# Altium_Demo_-_ADC_Schematic.net
KiCad netlist of a schematic drawn in Altium Designer
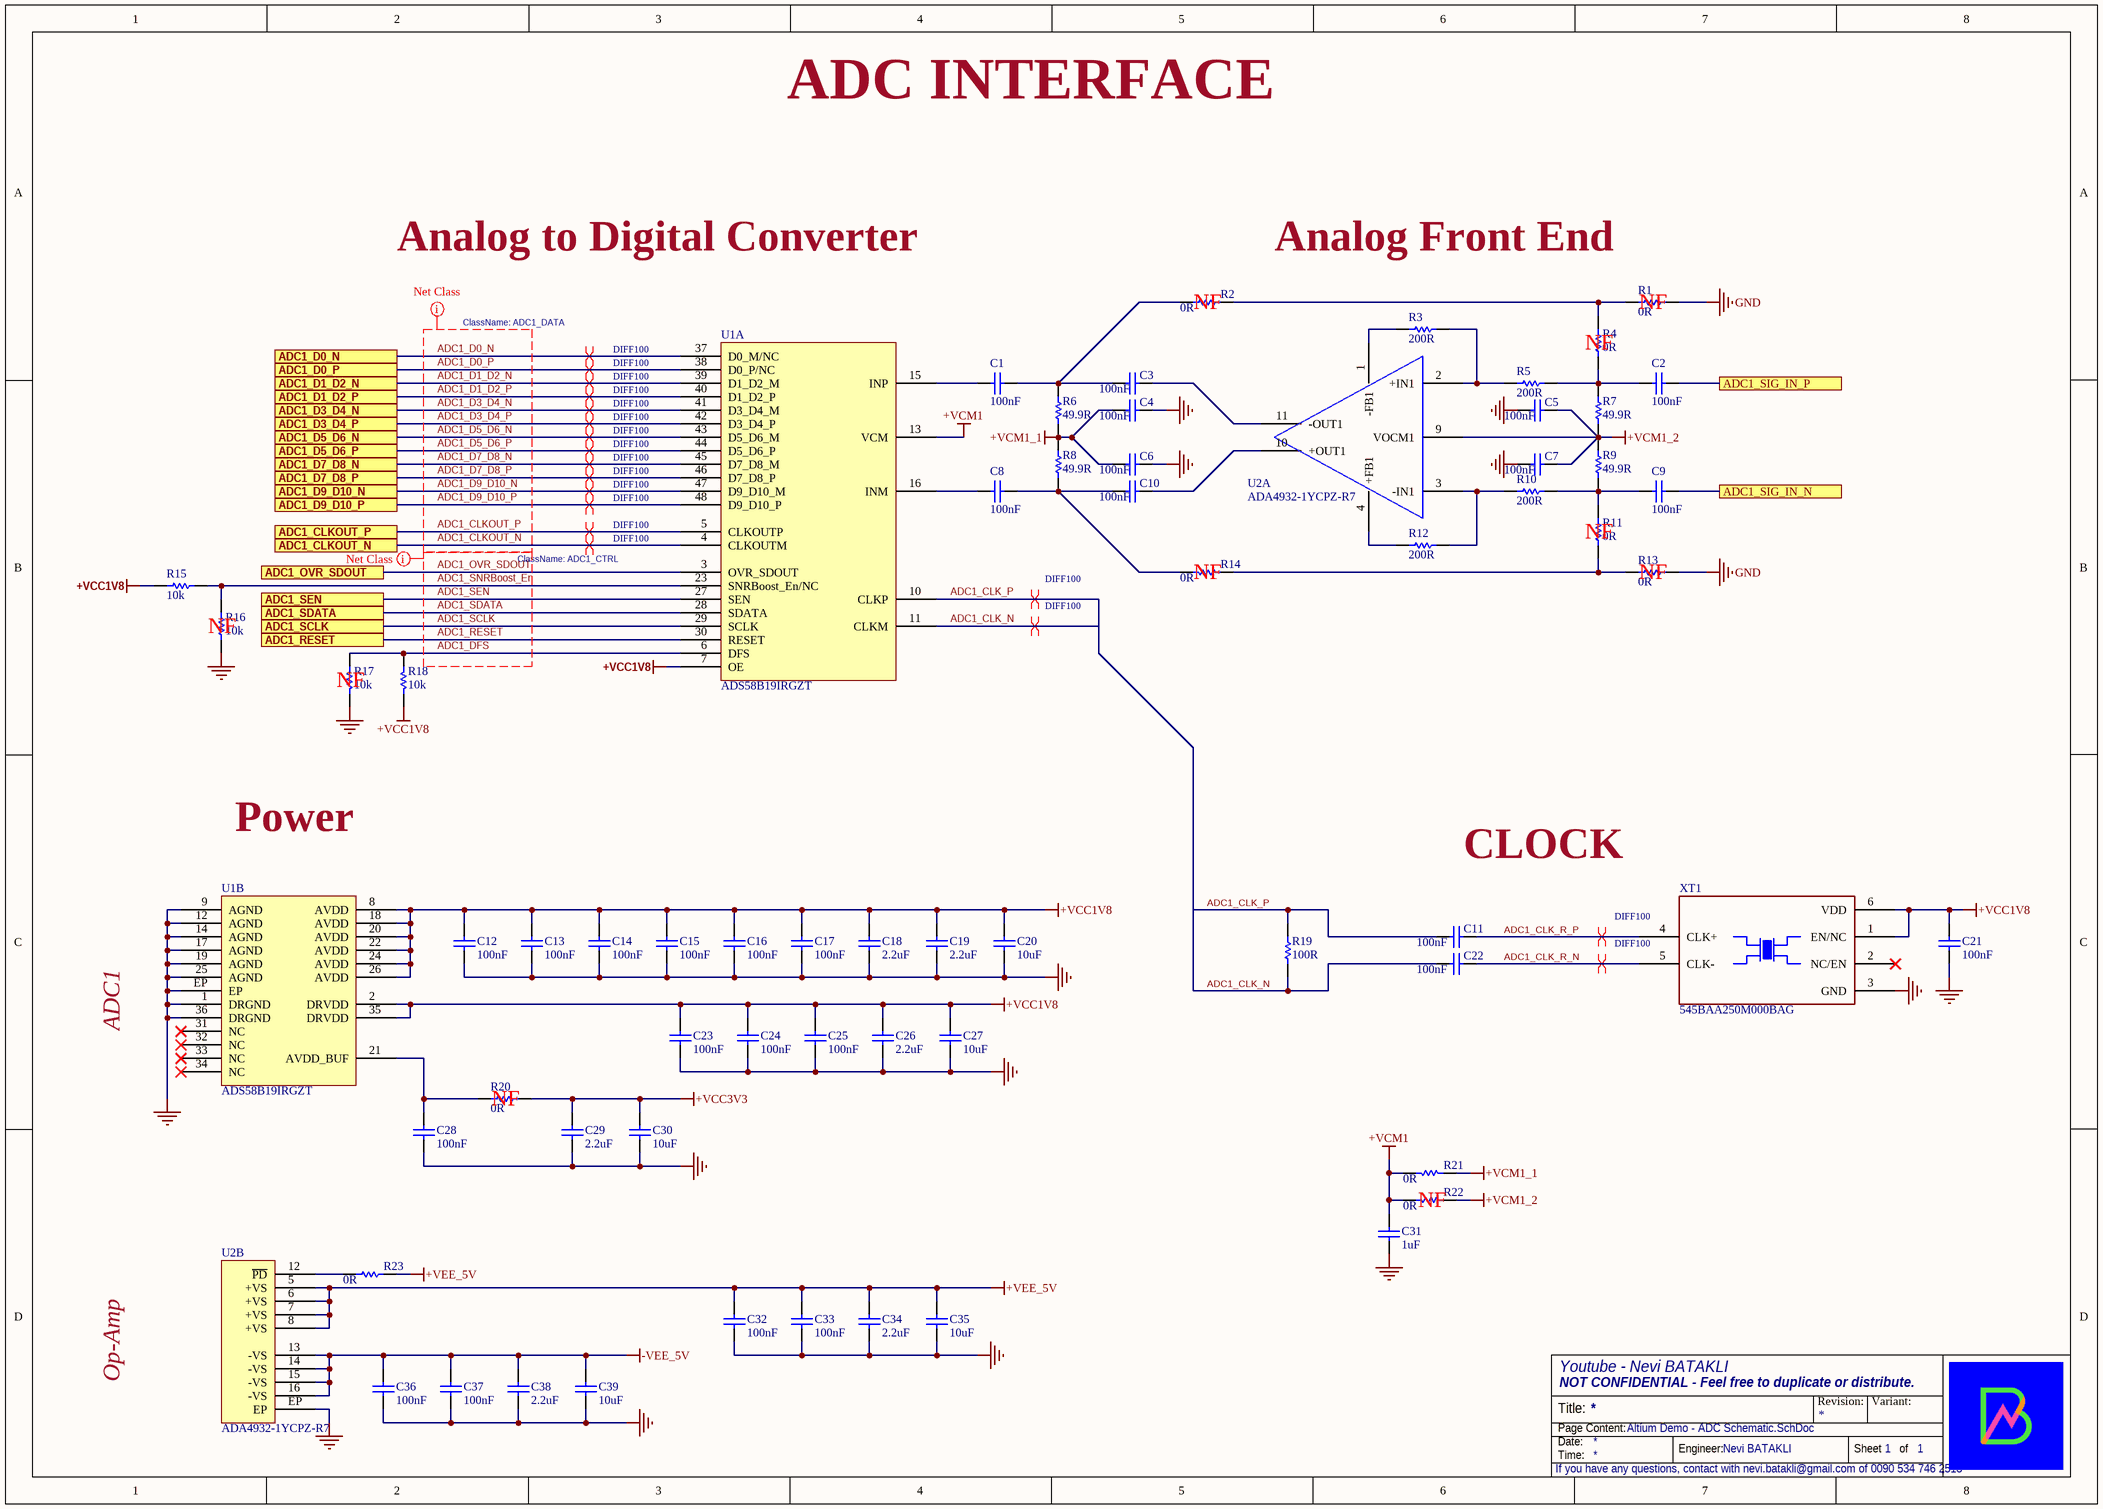
[diagram p0: Altium Demo - ADC Schematic.SchDoc]

(export (version "E")
  (design (tool "Eeschema 10.0.6"))
  (components
    (comp (ref "C1")
      (value "100nF")
      (footprint "R0201")
      (description "CAP CER 0.1UF 25V X6S 0201")
      (fields (field (name "TOLERANCE") "20%"))
      (libsource (lib "Capacitors") (part "GRM033C81E104ME14D"))
    )
    (comp (ref "C2")
      (value "100nF")
      (footprint "C0201")
      (description "CAP CER 0.1UF 25V X6S 0201")
      (fields (field (name "TOLERANCE") "20%"))
      (libsource (lib "Capacitors") (part "GRM033C81E104ME14D"))
    )
    (comp (ref "C3")
      (value "100nF")
      (footprint "C0201")
      (description "CAP CER 0.1UF 25V X6S 0201")
      (fields (field (name "TOLERANCE") "20%"))
      (libsource (lib "Capacitors") (part "GRM033C81E104ME14D"))
    )
    (comp (ref "C4")
      (value "100nF")
      (footprint "C0402")
      (description "Cap Ceramic 0.1uF 16V X7R 10% SMD 0402 125C Paper T/R")
      (fields
        (field (name "MANUFACTURER") "Samsung")
        (field (name "MANUFACTURER PART NUMBER") "CL05B104KO5NNNC")
        (field (name ".CREATOR") "NB")
      )
      (libsource (lib "Capacitors") (part "CL05B104KO5NNNC"))
    )
    (comp (ref "C5")
      (value "100nF")
      (footprint "C0402")
      (description "Cap Ceramic 0.1uF 16V X7R 10% SMD 0402 125C Paper T/R")
      (fields
        (field (name "MANUFACTURER") "Samsung")
        (field (name "MANUFACTURER PART NUMBER") "CL05B104KO5NNNC")
        (field (name ".CREATOR") "NB")
      )
      (libsource (lib "Capacitors") (part "CL05B104KO5NNNC"))
    )
    (comp (ref "C6")
      (value "100nF")
      (footprint "C0402")
      (description "Cap Ceramic 0.1uF 16V X7R 10% SMD 0402 125C Paper T/R")
      (fields
        (field (name "MANUFACTURER") "Samsung")
        (field (name "MANUFACTURER PART NUMBER") "CL05B104KO5NNNC")
        (field (name ".CREATOR") "NB")
      )
      (libsource (lib "Capacitors") (part "CL05B104KO5NNNC"))
    )
    (comp (ref "C7")
      (value "100nF")
      (footprint "C0402")
      (description "Cap Ceramic 0.1uF 16V X7R 10% SMD 0402 125C Paper T/R")
      (fields
        (field (name "MANUFACTURER") "Samsung")
        (field (name "MANUFACTURER PART NUMBER") "CL05B104KO5NNNC")
        (field (name ".CREATOR") "NB")
      )
      (libsource (lib "Capacitors") (part "CL05B104KO5NNNC"))
    )
    (comp (ref "C8")
      (value "100nF")
      (footprint "R0201")
      (description "CAP CER 0.1UF 25V X6S 0201")
      (fields (field (name "TOLERANCE") "20%"))
      (libsource (lib "Capacitors") (part "GRM033C81E104ME14D"))
    )
    (comp (ref "C9")
      (value "100nF")
      (footprint "C0201")
      (description "CAP CER 0.1UF 25V X6S 0201")
      (fields (field (name "TOLERANCE") "20%"))
      (libsource (lib "Capacitors") (part "GRM033C81E104ME14D"))
    )
    (comp (ref "C10")
      (value "100nF")
      (footprint "C0201")
      (description "CAP CER 0.1UF 25V X6S 0201")
      (fields (field (name "TOLERANCE") "20%"))
      (libsource (lib "Capacitors") (part "GRM033C81E104ME14D"))
    )
    (comp (ref "C11")
      (value "100nF")
      (footprint "C0402")
      (description "Cap Ceramic 0.1uF 16V X7R 10% SMD 0402 125C Paper T/R")
      (fields
        (field (name "MANUFACTURER") "Samsung")
        (field (name "MANUFACTURER PART NUMBER") "CL05B104KO5NNNC")
        (field (name ".CREATOR") "NB")
      )
      (libsource (lib "Capacitors") (part "CL05B104KO5NNNC"))
    )
    (comp (ref "C12")
      (value "100nF")
      (footprint "C0402")
      (description "Cap Ceramic 0.1uF 16V X7R 10% SMD 0402 125C Paper T/R")
      (fields
        (field (name "MANUFACTURER") "Samsung")
        (field (name "MANUFACTURER PART NUMBER") "CL05B104KO5NNNC")
        (field (name ".CREATOR") "NB")
      )
      (libsource (lib "Capacitors") (part "CL05B104KO5NNNC"))
    )
    (comp (ref "C13")
      (value "100nF")
      (footprint "C0402")
      (description "Cap Ceramic 0.1uF 16V X7R 10% SMD 0402 125C Paper T/R")
      (fields
        (field (name "MANUFACTURER") "Samsung")
        (field (name "MANUFACTURER PART NUMBER") "CL05B104KO5NNNC")
        (field (name ".CREATOR") "NB")
      )
      (libsource (lib "Capacitors") (part "CL05B104KO5NNNC"))
    )
    (comp (ref "C14")
      (value "100nF")
      (footprint "C0402")
      (description "Cap Ceramic 0.1uF 16V X7R 10% SMD 0402 125C Paper T/R")
      (fields
        (field (name "MANUFACTURER") "Samsung")
        (field (name "MANUFACTURER PART NUMBER") "CL05B104KO5NNNC")
        (field (name ".CREATOR") "NB")
      )
      (libsource (lib "Capacitors") (part "CL05B104KO5NNNC"))
    )
    (comp (ref "C15")
      (value "100nF")
      (footprint "C0402")
      (description "Cap Ceramic 0.1uF 16V X7R 10% SMD 0402 125C Paper T/R")
      (fields
        (field (name "MANUFACTURER") "Samsung")
        (field (name "MANUFACTURER PART NUMBER") "CL05B104KO5NNNC")
        (field (name ".CREATOR") "NB")
      )
      (libsource (lib "Capacitors") (part "CL05B104KO5NNNC"))
    )
    (comp (ref "C16")
      (value "100nF")
      (footprint "C0402")
      (description "Cap Ceramic 0.1uF 16V X7R 10% SMD 0402 125C Paper T/R")
      (fields
        (field (name "MANUFACTURER") "Samsung")
        (field (name "MANUFACTURER PART NUMBER") "CL05B104KO5NNNC")
        (field (name ".CREATOR") "NB")
      )
      (libsource (lib "Capacitors") (part "CL05B104KO5NNNC"))
    )
    (comp (ref "C17")
      (value "100nF")
      (footprint "C0402")
      (description "Cap Ceramic 0.1uF 16V X7R 10% SMD 0402 125C Paper T/R")
      (fields
        (field (name "MANUFACTURER") "Samsung")
        (field (name "MANUFACTURER PART NUMBER") "CL05B104KO5NNNC")
        (field (name ".CREATOR") "NB")
      )
      (libsource (lib "Capacitors") (part "CL05B104KO5NNNC"))
    )
    (comp (ref "C18")
      (value "2.2uF")
      (footprint "C0603")
      (description "Cap Ceramic 2.2uF 16V X5R 10% SMD 0603 85C Paper T/R")
      (fields
        (field (name "MANUFACTURER") "Samsung")
        (field (name "MANUFACTURER PART NUMBER") "CL10A225KO8NNNC")
        (field (name ".CREATOR") "NB")
      )
      (libsource (lib "Capacitors") (part "CL10A225KO8NNNC"))
    )
    (comp (ref "C19")
      (value "2.2uF")
      (footprint "C0603")
      (description "Cap Ceramic 2.2uF 16V X5R 10% SMD 0603 85C Paper T/R")
      (fields
        (field (name "MANUFACTURER") "Samsung")
        (field (name "MANUFACTURER PART NUMBER") "CL10A225KO8NNNC")
        (field (name ".CREATOR") "NB")
      )
      (libsource (lib "Capacitors") (part "CL10A225KO8NNNC"))
    )
    (comp (ref "C20")
      (value "10uF")
      (footprint "C0805")
      (description "CAP CER 10UF 16V X5R 0805")
      (fields
        (field (name "MANUFACTURER") "Samsung")
        (field (name "MANUFACTURER PART NUMBER") "CL21A106KOQNNNG")
        (field (name ".CREATOR") "NB")
      )
      (libsource (lib "Capacitors") (part "CL21A106KOQNNNG"))
    )
    (comp (ref "C21")
      (value "100nF")
      (footprint "C0402")
      (description "Cap Ceramic 0.1uF 16V X7R 10% SMD 0402 125C Paper T/R")
      (fields
        (field (name "MANUFACTURER") "Samsung")
        (field (name "MANUFACTURER PART NUMBER") "CL05B104KO5NNNC")
        (field (name ".CREATOR") "NB")
      )
      (libsource (lib "Capacitors") (part "CL05B104KO5NNNC"))
    )
    (comp (ref "C22")
      (value "100nF")
      (footprint "C0402")
      (description "Cap Ceramic 0.1uF 16V X7R 10% SMD 0402 125C Paper T/R")
      (fields
        (field (name "MANUFACTURER") "Samsung")
        (field (name "MANUFACTURER PART NUMBER") "CL05B104KO5NNNC")
        (field (name ".CREATOR") "NB")
      )
      (libsource (lib "Capacitors") (part "CL05B104KO5NNNC"))
    )
    (comp (ref "C23")
      (value "100nF")
      (footprint "C0402")
      (description "Cap Ceramic 0.1uF 16V X7R 10% SMD 0402 125C Paper T/R")
      (fields
        (field (name "MANUFACTURER") "Samsung")
        (field (name "MANUFACTURER PART NUMBER") "CL05B104KO5NNNC")
        (field (name ".CREATOR") "NB")
      )
      (libsource (lib "Capacitors") (part "CL05B104KO5NNNC"))
    )
    (comp (ref "C24")
      (value "100nF")
      (footprint "C0402")
      (description "Cap Ceramic 0.1uF 16V X7R 10% SMD 0402 125C Paper T/R")
      (fields
        (field (name "MANUFACTURER") "Samsung")
        (field (name "MANUFACTURER PART NUMBER") "CL05B104KO5NNNC")
        (field (name ".CREATOR") "NB")
      )
      (libsource (lib "Capacitors") (part "CL05B104KO5NNNC"))
    )
    (comp (ref "C25")
      (value "100nF")
      (footprint "C0402")
      (description "Cap Ceramic 0.1uF 16V X7R 10% SMD 0402 125C Paper T/R")
      (fields
        (field (name "MANUFACTURER") "Samsung")
        (field (name "MANUFACTURER PART NUMBER") "CL05B104KO5NNNC")
        (field (name ".CREATOR") "NB")
      )
      (libsource (lib "Capacitors") (part "CL05B104KO5NNNC"))
    )
    (comp (ref "C26")
      (value "2.2uF")
      (footprint "C0603")
      (description "Cap Ceramic 2.2uF 16V X5R 10% SMD 0603 85C Paper T/R")
      (fields
        (field (name "MANUFACTURER") "Samsung")
        (field (name "MANUFACTURER PART NUMBER") "CL10A225KO8NNNC")
        (field (name ".CREATOR") "NB")
      )
      (libsource (lib "Capacitors") (part "CL10A225KO8NNNC"))
    )
    (comp (ref "C27")
      (value "10uF")
      (footprint "C0805")
      (description "CAP CER 10UF 16V X5R 0805")
      (fields
        (field (name "MANUFACTURER") "Samsung")
        (field (name "MANUFACTURER PART NUMBER") "CL21A106KOQNNNG")
        (field (name ".CREATOR") "NB")
      )
      (libsource (lib "Capacitors") (part "CL21A106KOQNNNG"))
    )
    (comp (ref "C28")
      (value "100nF")
      (footprint "C0402")
      (description "Cap Ceramic 0.1uF 16V X7R 10% SMD 0402 125C Paper T/R")
      (fields
        (field (name "MANUFACTURER") "Samsung")
        (field (name "MANUFACTURER PART NUMBER") "CL05B104KO5NNNC")
        (field (name ".CREATOR") "NB")
      )
      (libsource (lib "Capacitors") (part "CL05B104KO5NNNC"))
    )
    (comp (ref "C29")
      (value "2.2uF")
      (footprint "C0603")
      (description "Cap Ceramic 2.2uF 16V X5R 10% SMD 0603 85C Paper T/R")
      (fields
        (field (name "MANUFACTURER") "Samsung")
        (field (name "MANUFACTURER PART NUMBER") "CL10A225KO8NNNC")
        (field (name ".CREATOR") "NB")
      )
      (libsource (lib "Capacitors") (part "CL10A225KO8NNNC"))
    )
    (comp (ref "C30")
      (value "10uF")
      (footprint "C0805")
      (description "CAP CER 10UF 16V X5R 0805")
      (fields
        (field (name "MANUFACTURER") "Samsung")
        (field (name "MANUFACTURER PART NUMBER") "CL21A106KOQNNNG")
        (field (name ".CREATOR") "NB")
      )
      (libsource (lib "Capacitors") (part "CL21A106KOQNNNG"))
    )
    (comp (ref "C31")
      (value "1uF")
      (footprint "C0603")
      (description "Cap Ceramic 0.1uF 16V X7R 10% SMD 0402 125C Automotive Cardboard T/R")
      (fields
        (field (name "MANUFACTURER") "Samsung")
        (field (name "MANUFACTURER PART NUMBER") "CL05B104KO5VPNC")
        (field (name ".CREATOR") "NB")
      )
      (libsource (lib "Capacitors") (part "CL05B104KO5VPNC"))
    )
    (comp (ref "C32")
      (value "100nF")
      (footprint "C0402")
      (description "Cap Ceramic 0.1uF 16V X7R 10% SMD 0402 125C Paper T/R")
      (fields
        (field (name "MANUFACTURER") "Samsung")
        (field (name "MANUFACTURER PART NUMBER") "CL05B104KO5NNNC")
        (field (name ".CREATOR") "NB")
      )
      (libsource (lib "Capacitors") (part "CL05B104KO5NNNC"))
    )
    (comp (ref "C33")
      (value "100nF")
      (footprint "C0402")
      (description "Cap Ceramic 0.1uF 16V X7R 10% SMD 0402 125C Paper T/R")
      (fields
        (field (name "MANUFACTURER") "Samsung")
        (field (name "MANUFACTURER PART NUMBER") "CL05B104KO5NNNC")
        (field (name ".CREATOR") "NB")
      )
      (libsource (lib "Capacitors") (part "CL05B104KO5NNNC"))
    )
    (comp (ref "C34")
      (value "2.2uF")
      (footprint "C0603")
      (description "Cap Ceramic 2.2uF 16V X5R 10% SMD 0603 85C Paper T/R")
      (fields
        (field (name "MANUFACTURER") "Samsung")
        (field (name "MANUFACTURER PART NUMBER") "CL10A225KO8NNNC")
        (field (name ".CREATOR") "NB")
      )
      (libsource (lib "Capacitors") (part "CL10A225KO8NNNC"))
    )
    (comp (ref "C35")
      (value "10uF")
      (footprint "C0805")
      (description "CAP CER 10UF 16V X5R 0805")
      (fields
        (field (name "MANUFACTURER") "Samsung")
        (field (name "MANUFACTURER PART NUMBER") "CL21A106KOQNNNG")
        (field (name ".CREATOR") "NB")
      )
      (libsource (lib "Capacitors") (part "CL21A106KOQNNNG"))
    )
    (comp (ref "C36")
      (value "100nF")
      (footprint "C0402")
      (description "Cap Ceramic 0.1uF 16V X7R 10% SMD 0402 125C Paper T/R")
      (fields
        (field (name "MANUFACTURER") "Samsung")
        (field (name "MANUFACTURER PART NUMBER") "CL05B104KO5NNNC")
        (field (name ".CREATOR") "NB")
      )
      (libsource (lib "Capacitors") (part "CL05B104KO5NNNC"))
    )
    (comp (ref "C37")
      (value "100nF")
      (footprint "C0402")
      (description "Cap Ceramic 0.1uF 16V X7R 10% SMD 0402 125C Paper T/R")
      (fields
        (field (name "MANUFACTURER") "Samsung")
        (field (name "MANUFACTURER PART NUMBER") "CL05B104KO5NNNC")
        (field (name ".CREATOR") "NB")
      )
      (libsource (lib "Capacitors") (part "CL05B104KO5NNNC"))
    )
    (comp (ref "C38")
      (value "2.2uF")
      (footprint "C0603")
      (description "Cap Ceramic 2.2uF 16V X5R 10% SMD 0603 85C Paper T/R")
      (fields
        (field (name "MANUFACTURER") "Samsung")
        (field (name "MANUFACTURER PART NUMBER") "CL10A225KO8NNNC")
        (field (name ".CREATOR") "NB")
      )
      (libsource (lib "Capacitors") (part "CL10A225KO8NNNC"))
    )
    (comp (ref "C39")
      (value "10uF")
      (footprint "C0805")
      (description "CAP CER 10UF 16V X5R 0805")
      (fields
        (field (name "MANUFACTURER") "Samsung")
        (field (name "MANUFACTURER PART NUMBER") "CL21A106KOQNNNG")
        (field (name ".CREATOR") "NB")
      )
      (libsource (lib "Capacitors") (part "CL21A106KOQNNNG"))
    )
    (comp (ref "R1")
      (value "0R")
      (footprint "R0402")
      (description "RES SMD 0.0OHM JUMPER 1/16W 0402")
      (fields
        (field (name "MANUFACTURER") "Yageo")
        (field (name "MANUFACTURER PART NUMBER") "RC0402JR-070RL")
        (field (name ".CREATOR") "NB")
      )
      (libsource (lib "Resistors") (part "RC0402JR-070RL"))
    )
    (comp (ref "R2")
      (value "0R")
      (footprint "R0402")
      (description "RES SMD 0.0OHM JUMPER 1/16W 0402")
      (fields
        (field (name "MANUFACTURER") "Yageo")
        (field (name "MANUFACTURER PART NUMBER") "RC0402JR-070RL")
        (field (name ".CREATOR") "NB")
      )
      (libsource (lib "Resistors") (part "RC0402JR-070RL"))
    )
    (comp (ref "R3")
      (value "200R")
      (footprint "R0402")
      (description "RES SMD 200 OHM 1% 1/16W 0402")
      (fields (field (name "TOLERANCE") "1%"))
      (libsource (lib "Resistors") (part "RC0402FR-07200RL"))
    )
    (comp (ref "R4")
      (value "0R")
      (footprint "R0402")
      (description "RES SMD 0.0OHM JUMPER 1/16W 0402")
      (fields
        (field (name "MANUFACTURER") "Yageo")
        (field (name "MANUFACTURER PART NUMBER") "RC0402JR-070RL")
        (field (name ".CREATOR") "NB")
      )
      (libsource (lib "Resistors") (part "RC0402JR-070RL"))
    )
    (comp (ref "R5")
      (value "200R")
      (footprint "R0402")
      (description "RES SMD 200 OHM 1% 1/16W 0402")
      (fields (field (name "TOLERANCE") "1%"))
      (libsource (lib "Resistors") (part "RC0402FR-07200RL"))
    )
    (comp (ref "R6")
      (value "49.9R")
      (footprint "R0201")
      (fields (field (name ".CREATOR") "NB") (field (name ".SCHCHECKED") "NB"))
      (libsource (lib "SCH Library") (part "Res_DNP"))
    )
    (comp (ref "R7")
      (value "49.9R")
      (footprint "R0402")
      (description "RES SMD 49.9 OHM 1% 1/16W 0402")
      (fields (field (name "TOLERANCE") "1%"))
      (libsource (lib "Resistors") (part "RC0402FR-0749R9L"))
    )
    (comp (ref "R8")
      (value "49.9R")
      (footprint "R0201")
      (fields (field (name ".CREATOR") "NB") (field (name ".SCHCHECKED") "NB"))
      (libsource (lib "SCH Library") (part "Res_DNP"))
    )
    (comp (ref "R9")
      (value "49.9R")
      (footprint "R0402")
      (description "RES SMD 49.9 OHM 1% 1/16W 0402")
      (fields (field (name "TOLERANCE") "1%"))
      (libsource (lib "Resistors") (part "RC0402FR-0749R9L"))
    )
    (comp (ref "R10")
      (value "200R")
      (footprint "R0402")
      (description "RES SMD 200 OHM 1% 1/16W 0402")
      (fields (field (name "TOLERANCE") "1%"))
      (libsource (lib "Resistors") (part "RC0402FR-07200RL"))
    )
    (comp (ref "R11")
      (value "0R")
      (footprint "R0402")
      (description "RES SMD 0.0OHM JUMPER 1/16W 0402")
      (fields
        (field (name "MANUFACTURER") "Yageo")
        (field (name "MANUFACTURER PART NUMBER") "RC0402JR-070RL")
        (field (name ".CREATOR") "NB")
      )
      (libsource (lib "Resistors") (part "RC0402JR-070RL"))
    )
    (comp (ref "R12")
      (value "200R")
      (footprint "R0402")
      (description "RES SMD 200 OHM 1% 1/16W 0402")
      (fields (field (name "TOLERANCE") "1%"))
      (libsource (lib "Resistors") (part "RC0402FR-07200RL"))
    )
    (comp (ref "R13")
      (value "0R")
      (footprint "R0402")
      (description "RES SMD 0.0OHM JUMPER 1/16W 0402")
      (fields
        (field (name "MANUFACTURER") "Yageo")
        (field (name "MANUFACTURER PART NUMBER") "RC0402JR-070RL")
        (field (name ".CREATOR") "NB")
      )
      (libsource (lib "Resistors") (part "RC0402JR-070RL"))
    )
    (comp (ref "R14")
      (value "0R")
      (footprint "R0402")
      (description "RES SMD 0.0OHM JUMPER 1/16W 0402")
      (fields
        (field (name "MANUFACTURER") "Yageo")
        (field (name "MANUFACTURER PART NUMBER") "RC0402JR-070RL")
        (field (name ".CREATOR") "NB")
      )
      (libsource (lib "Resistors") (part "RC0402JR-070RL"))
    )
    (comp (ref "R15")
      (value "10k")
      (footprint "R0402")
      (description "Yageo RC Series Thick Film Surface Mount Resistor 0402 Case 10000 1% 0.063W 100ppm/C")
      (fields
        (field (name "MANUFACTURER") "Yageo Phycomp")
        (field (name "MANUFACTURER PART NUMBER") "RC0402FR-0710KL")
        (field (name ".CREATOR") "NB")
      )
      (libsource (lib "Resistors") (part "RC0402FR-0710KL"))
    )
    (comp (ref "R16")
      (value "10k")
      (footprint "R0402")
      (description "Yageo RC Series Thick Film Surface Mount Resistor 0402 Case 10000 1% 0.063W 100ppm/C")
      (fields
        (field (name "MANUFACTURER") "Yageo Phycomp")
        (field (name "MANUFACTURER PART NUMBER") "RC0402FR-0710KL")
        (field (name ".CREATOR") "NB")
      )
      (libsource (lib "Resistors") (part "RC0402FR-0710KL"))
    )
    (comp (ref "R17")
      (value "10k")
      (footprint "R0402")
      (description "Yageo RC Series Thick Film Surface Mount Resistor 0402 Case 10000 1% 0.063W 100ppm/C")
      (fields
        (field (name "MANUFACTURER") "Yageo Phycomp")
        (field (name "MANUFACTURER PART NUMBER") "RC0402FR-0710KL")
        (field (name ".CREATOR") "NB")
      )
      (libsource (lib "Resistors") (part "RC0402FR-0710KL"))
    )
    (comp (ref "R18")
      (value "10k")
      (footprint "R0402")
      (description "Yageo RC Series Thick Film Surface Mount Resistor 0402 Case 10000 1% 0.063W 100ppm/C")
      (fields
        (field (name "MANUFACTURER") "Yageo Phycomp")
        (field (name "MANUFACTURER PART NUMBER") "RC0402FR-0710KL")
        (field (name ".CREATOR") "NB")
      )
      (libsource (lib "Resistors") (part "RC0402FR-0710KL"))
    )
    (comp (ref "R19")
      (value "100R")
      (footprint "R0402")
      (description "RES SMD 100 OHM 1% 1/16W 0402")
      (fields (field (name "TOLERANCE") "1%"))
      (libsource (lib "Resistors") (part "RC0402FR-07100RL"))
    )
    (comp (ref "R20")
      (value "0R")
      (footprint "R0402")
      (description "RES SMD 0.0OHM JUMPER 1/16W 0402")
      (fields
        (field (name "MANUFACTURER") "Yageo")
        (field (name "MANUFACTURER PART NUMBER") "RC0402JR-070RL")
        (field (name ".CREATOR") "NB")
      )
      (libsource (lib "Resistors") (part "RC0402JR-070RL"))
    )
    (comp (ref "R21")
      (value "0R")
      (footprint "R0402")
      (description "RES SMD 0.0OHM JUMPER 1/16W 0402")
      (fields
        (field (name "MANUFACTURER") "Yageo")
        (field (name "MANUFACTURER PART NUMBER") "RC0402JR-070RL")
        (field (name ".CREATOR") "NB")
      )
      (libsource (lib "Resistors") (part "RC0402JR-070RL"))
    )
    (comp (ref "R22")
      (value "0R")
      (footprint "R0402")
      (description "RES SMD 0.0OHM JUMPER 1/16W 0402")
      (fields
        (field (name "MANUFACTURER") "Yageo")
        (field (name "MANUFACTURER PART NUMBER") "RC0402JR-070RL")
        (field (name ".CREATOR") "NB")
      )
      (libsource (lib "Resistors") (part "RC0402JR-070RL"))
    )
    (comp (ref "R23")
      (value "0R")
      (footprint "R0402")
      (description "RES SMD 0.0OHM JUMPER 1/16W 0402")
      (fields
        (field (name "MANUFACTURER") "Yageo")
        (field (name "MANUFACTURER PART NUMBER") "RC0402JR-070RL")
        (field (name ".CREATOR") "NB")
      )
      (libsource (lib "Resistors") (part "RC0402JR-070RL"))
    )
    (comp (ref "U1")
      (value "ADS58B19IRGZT")
      (footprint "VFQFN-48 (7x7)")
      (description "IC ADC 9BIT 250MSPS 48VQFN")
      (fields (field (name "MANUFACTURER") "Texas Instruments"))
      (libsource (lib "Sheet1") (part "ADS58B19IRGZT"))
    )
    (comp (ref "U2")
      (value "ADA4932-1YCPZ-R7")
      (footprint "VFQFN16 (3x3)")
      (description "IC OPAMP DIFF 560MHZ 16LFCSP")
      (fields (field (name "MANUFACTURER") "Analog Devices") (field (name ".CREATOR") "NB"))
      (libsource (lib "Integrated Circuits") (part "ADA4932-1YCPZ-R7"))
    )
    (comp (ref "XT1")
      (value "545BAA250M000BAG")
      (footprint "Si545")
      (description "XTAL OSC XO 250.0000MHZ LVDS SMD")
      (fields (field (name "MANUFACTURER") "Silicon Labs") (field (name ".CREATOR") "NB"))
      (libsource (lib "Oscillators") (part "545BAA250M000BAG"))
    )
  )
  (nets
    (net (code "1") (name "+VCC1V8") (class "Default")
      (node (ref "C12") (pin "1") (pinfunction "1_1") (pintype "passive"))
      (node (ref "C13") (pin "1") (pinfunction "1_1") (pintype "passive"))
      (node (ref "C14") (pin "1") (pinfunction "1_1") (pintype "passive"))
      (node (ref "C15") (pin "1") (pinfunction "1_1") (pintype "passive"))
      (node (ref "C16") (pin "1") (pinfunction "1_1") (pintype "passive"))
      (node (ref "C17") (pin "1") (pinfunction "1_1") (pintype "passive"))
      (node (ref "C18") (pin "1") (pinfunction "1_1") (pintype "passive"))
      (node (ref "C19") (pin "1") (pinfunction "1_1") (pintype "passive"))
      (node (ref "C20") (pin "1") (pinfunction "1_1") (pintype "passive"))
      (node (ref "C21") (pin "1") (pinfunction "1_1") (pintype "passive"))
      (node (ref "C23") (pin "1") (pinfunction "1_1") (pintype "passive"))
      (node (ref "C24") (pin "1") (pinfunction "1_1") (pintype "passive"))
      (node (ref "C25") (pin "1") (pinfunction "1_1") (pintype "passive"))
      (node (ref "C26") (pin "1") (pinfunction "1_1") (pintype "passive"))
      (node (ref "C27") (pin "1") (pinfunction "1_1") (pintype "passive"))
      (node (ref "R15") (pin "2") (pinfunction "2_2") (pintype "passive"))
      (node (ref "R18") (pin "2") (pinfunction "2_2") (pintype "passive"))
      (node (ref "U1") (pin "18") (pinfunction "AVDD_18") (pintype "passive"))
      (node (ref "U1") (pin "2") (pinfunction "DRVDD_2") (pintype "passive"))
      (node (ref "U1") (pin "20") (pinfunction "AVDD_20") (pintype "passive"))
      (node (ref "U1") (pin "22") (pinfunction "AVDD_22") (pintype "passive"))
      (node (ref "U1") (pin "24") (pinfunction "AVDD_24") (pintype "passive"))
      (node (ref "U1") (pin "26") (pinfunction "AVDD_26") (pintype "passive"))
      (node (ref "U1") (pin "35") (pinfunction "DRVDD_35") (pintype "passive"))
      (node (ref "U1") (pin "7") (pinfunction "OE_7") (pintype "passive"))
      (node (ref "U1") (pin "8") (pinfunction "AVDD_8") (pintype "passive"))
      (node (ref "XT1") (pin "1") (pinfunction "EN/NC_1") (pintype "passive"))
      (node (ref "XT1") (pin "6") (pinfunction "VDD_6") (pintype "passive"))
    )
    (net (code "2") (name "+VCC3V3") (class "Default")
      (node (ref "C29") (pin "1") (pinfunction "1_1") (pintype "passive"))
      (node (ref "C30") (pin "1") (pinfunction "1_1") (pintype "passive"))
      (node (ref "R20") (pin "1") (pinfunction "1_1") (pintype "passive"))
    )
    (net (code "3") (name "+VCM1") (class "Default")
      (node (ref "C31") (pin "1") (pinfunction "1_1") (pintype "passive"))
      (node (ref "R21") (pin "2") (pinfunction "2_2") (pintype "passive"))
      (node (ref "R22") (pin "2") (pinfunction "2_2") (pintype "passive"))
      (node (ref "U1") (pin "13") (pinfunction "VCM_13") (pintype "passive"))
    )
    (net (code "4") (name "+VCM1_1") (class "Default")
      (node (ref "C4") (pin "2") (pinfunction "2_2") (pintype "passive"))
      (node (ref "C6") (pin "2") (pinfunction "2_2") (pintype "passive"))
      (node (ref "R21") (pin "1") (pinfunction "1_1") (pintype "passive"))
      (node (ref "R6") (pin "1") (pinfunction "1_1") (pintype "passive"))
      (node (ref "R8") (pin "2") (pinfunction "2_2") (pintype "passive"))
    )
    (net (code "5") (name "+VCM1_2") (class "Default")
      (node (ref "C5") (pin "1") (pinfunction "1_1") (pintype "passive"))
      (node (ref "C7") (pin "1") (pinfunction "1_1") (pintype "passive"))
      (node (ref "R22") (pin "1") (pinfunction "1_1") (pintype "passive"))
      (node (ref "R7") (pin "1") (pinfunction "1_1") (pintype "passive"))
      (node (ref "R9") (pin "2") (pinfunction "2_2") (pintype "passive"))
      (node (ref "U2") (pin "9") (pinfunction "VOCM1_9") (pintype "passive"))
    )
    (net (code "6") (name "+VEE_5V") (class "Default")
      (node (ref "C32") (pin "1") (pinfunction "1_1") (pintype "passive"))
      (node (ref "C33") (pin "1") (pinfunction "1_1") (pintype "passive"))
      (node (ref "C34") (pin "1") (pinfunction "1_1") (pintype "passive"))
      (node (ref "C35") (pin "1") (pinfunction "1_1") (pintype "passive"))
      (node (ref "R23") (pin "1") (pinfunction "1_1") (pintype "passive"))
      (node (ref "U2") (pin "5") (pinfunction "+VS_5") (pintype "passive"))
      (node (ref "U2") (pin "6") (pinfunction "+VS_6") (pintype "passive"))
      (node (ref "U2") (pin "7") (pinfunction "+VS_7") (pintype "passive"))
      (node (ref "U2") (pin "8") (pinfunction "+VS_8") (pintype "passive"))
    )
    (net (code "7") (name "-VEE_5V") (class "Default")
      (node (ref "C36") (pin "1") (pinfunction "1_1") (pintype "passive"))
      (node (ref "C37") (pin "1") (pinfunction "1_1") (pintype "passive"))
      (node (ref "C38") (pin "1") (pinfunction "1_1") (pintype "passive"))
      (node (ref "C39") (pin "1") (pinfunction "1_1") (pintype "passive"))
      (node (ref "U2") (pin "13") (pinfunction "-VS_13") (pintype "passive"))
      (node (ref "U2") (pin "14") (pinfunction "-VS_14") (pintype "passive"))
      (node (ref "U2") (pin "15") (pinfunction "-VS_15") (pintype "passive"))
      (node (ref "U2") (pin "16") (pinfunction "-VS_16") (pintype "passive"))
    )
    (net (code "8") (name "/ADC1_CLKOUT_N") (class "Default")
      (node (ref "U1") (pin "4") (pinfunction "CLKOUTM_4") (pintype "passive"))
    )
    (net (code "9") (name "/ADC1_CLKOUT_P") (class "Default")
      (node (ref "U1") (pin "5") (pinfunction "CLKOUTP_5") (pintype "passive"))
    )
    (net (code "10") (name "/ADC1_CLK_N") (class "Default")
      (node (ref "C22") (pin "2") (pinfunction "2_2") (pintype "passive"))
      (node (ref "R19") (pin "1") (pinfunction "1_1") (pintype "passive"))
      (node (ref "U1") (pin "11") (pinfunction "CLKM_11") (pintype "passive"))
    )
    (net (code "11") (name "/ADC1_CLK_P") (class "Default")
      (node (ref "C11") (pin "2") (pinfunction "2_2") (pintype "passive"))
      (node (ref "R19") (pin "2") (pinfunction "2_2") (pintype "passive"))
      (node (ref "U1") (pin "10") (pinfunction "CLKP_10") (pintype "passive"))
    )
    (net (code "12") (name "/ADC1_CLK_R_N") (class "Default")
      (node (ref "C22") (pin "1") (pinfunction "1_1") (pintype "passive"))
      (node (ref "XT1") (pin "5") (pinfunction "CLK-_5") (pintype "passive"))
    )
    (net (code "13") (name "/ADC1_CLK_R_P") (class "Default")
      (node (ref "C11") (pin "1") (pinfunction "1_1") (pintype "passive"))
      (node (ref "XT1") (pin "4") (pinfunction "CLK+_4") (pintype "passive"))
    )
    (net (code "14") (name "/ADC1_D0_N") (class "Default")
      (node (ref "U1") (pin "37") (pinfunction "D0_M/NC_37") (pintype "passive"))
    )
    (net (code "15") (name "/ADC1_D0_P") (class "Default")
      (node (ref "U1") (pin "38") (pinfunction "D0_P/NC_38") (pintype "passive"))
    )
    (net (code "16") (name "/ADC1_D1_D2_N") (class "Default")
      (node (ref "U1") (pin "39") (pinfunction "D1_D2_M_39") (pintype "passive"))
    )
    (net (code "17") (name "/ADC1_D1_D2_P") (class "Default")
      (node (ref "U1") (pin "40") (pinfunction "D1_D2_P_40") (pintype "passive"))
    )
    (net (code "18") (name "/ADC1_D3_D4_N") (class "Default")
      (node (ref "U1") (pin "41") (pinfunction "D3_D4_M_41") (pintype "passive"))
    )
    (net (code "19") (name "/ADC1_D3_D4_P") (class "Default")
      (node (ref "U1") (pin "42") (pinfunction "D3_D4_P_42") (pintype "passive"))
    )
    (net (code "20") (name "/ADC1_D5_D6_N") (class "Default")
      (node (ref "U1") (pin "43") (pinfunction "D5_D6_M_43") (pintype "passive"))
    )
    (net (code "21") (name "/ADC1_D5_D6_P") (class "Default")
      (node (ref "U1") (pin "44") (pinfunction "D5_D6_P_44") (pintype "passive"))
    )
    (net (code "22") (name "/ADC1_D7_D8_N") (class "Default")
      (node (ref "U1") (pin "45") (pinfunction "D7_D8_M_45") (pintype "passive"))
    )
    (net (code "23") (name "/ADC1_D7_D8_P") (class "Default")
      (node (ref "U1") (pin "46") (pinfunction "D7_D8_P_46") (pintype "passive"))
    )
    (net (code "24") (name "/ADC1_D9_D10_N") (class "Default")
      (node (ref "U1") (pin "47") (pinfunction "D9_D10_M_47") (pintype "passive"))
    )
    (net (code "25") (name "/ADC1_D9_D10_P") (class "Default")
      (node (ref "U1") (pin "48") (pinfunction "D9_D10_P_48") (pintype "passive"))
    )
    (net (code "26") (name "/ADC1_DFS") (class "Default")
      (node (ref "R17") (pin "1") (pinfunction "1_1") (pintype "passive"))
      (node (ref "R18") (pin "1") (pinfunction "1_1") (pintype "passive"))
      (node (ref "U1") (pin "6") (pinfunction "DFS_6") (pintype "passive"))
    )
    (net (code "27") (name "/ADC1_OVR_SDOUT") (class "Default")
      (node (ref "U1") (pin "3") (pinfunction "OVR_SDOUT_3") (pintype "passive"))
    )
    (net (code "28") (name "/ADC1_RESET") (class "Default")
      (node (ref "U1") (pin "30") (pinfunction "RESET_30") (pintype "passive"))
    )
    (net (code "29") (name "/ADC1_SCLK") (class "Default")
      (node (ref "U1") (pin "29") (pinfunction "SCLK_29") (pintype "passive"))
    )
    (net (code "30") (name "/ADC1_SDATA") (class "Default")
      (node (ref "U1") (pin "28") (pinfunction "SDATA_28") (pintype "passive"))
    )
    (net (code "31") (name "/ADC1_SEN") (class "Default")
      (node (ref "U1") (pin "27") (pinfunction "SEN_27") (pintype "passive"))
    )
    (net (code "32") (name "/ADC1_SIG_IN_N") (class "Default")
      (node (ref "C9") (pin "2") (pinfunction "2_2") (pintype "passive"))
    )
    (net (code "33") (name "/ADC1_SIG_IN_P") (class "Default")
      (node (ref "C2") (pin "2") (pinfunction "2_2") (pintype "passive"))
    )
    (net (code "34") (name "/ADC1_SNRBoost_En") (class "Default")
      (node (ref "R15") (pin "1") (pinfunction "1_1") (pintype "passive"))
      (node (ref "R16") (pin "1") (pinfunction "1_1") (pintype "passive"))
      (node (ref "U1") (pin "23") (pinfunction "SNRBoost_En/NC_23") (pintype "passive"))
    )
    (net (code "35") (name "GND") (class "Default")
      (node (ref "C12") (pin "2") (pinfunction "2_2") (pintype "passive"))
      (node (ref "C13") (pin "2") (pinfunction "2_2") (pintype "passive"))
      (node (ref "C14") (pin "2") (pinfunction "2_2") (pintype "passive"))
      (node (ref "C15") (pin "2") (pinfunction "2_2") (pintype "passive"))
      (node (ref "C16") (pin "2") (pinfunction "2_2") (pintype "passive"))
      (node (ref "C17") (pin "2") (pinfunction "2_2") (pintype "passive"))
      (node (ref "C18") (pin "2") (pinfunction "2_2") (pintype "passive"))
      (node (ref "C19") (pin "2") (pinfunction "2_2") (pintype "passive"))
      (node (ref "C20") (pin "2") (pinfunction "2_2") (pintype "passive"))
      (node (ref "C21") (pin "2") (pinfunction "2_2") (pintype "passive"))
      (node (ref "C23") (pin "2") (pinfunction "2_2") (pintype "passive"))
      (node (ref "C24") (pin "2") (pinfunction "2_2") (pintype "passive"))
      (node (ref "C25") (pin "2") (pinfunction "2_2") (pintype "passive"))
      (node (ref "C26") (pin "2") (pinfunction "2_2") (pintype "passive"))
      (node (ref "C27") (pin "2") (pinfunction "2_2") (pintype "passive"))
      (node (ref "C28") (pin "2") (pinfunction "2_2") (pintype "passive"))
      (node (ref "C29") (pin "2") (pinfunction "2_2") (pintype "passive"))
      (node (ref "C30") (pin "2") (pinfunction "2_2") (pintype "passive"))
      (node (ref "C31") (pin "2") (pinfunction "2_2") (pintype "passive"))
      (node (ref "C32") (pin "2") (pinfunction "2_2") (pintype "passive"))
      (node (ref "C33") (pin "2") (pinfunction "2_2") (pintype "passive"))
      (node (ref "C34") (pin "2") (pinfunction "2_2") (pintype "passive"))
      (node (ref "C35") (pin "2") (pinfunction "2_2") (pintype "passive"))
      (node (ref "C36") (pin "2") (pinfunction "2_2") (pintype "passive"))
      (node (ref "C37") (pin "2") (pinfunction "2_2") (pintype "passive"))
      (node (ref "C38") (pin "2") (pinfunction "2_2") (pintype "passive"))
      (node (ref "C39") (pin "2") (pinfunction "2_2") (pintype "passive"))
      (node (ref "C4") (pin "1") (pinfunction "1_1") (pintype "passive"))
      (node (ref "C5") (pin "2") (pinfunction "2_2") (pintype "passive"))
      (node (ref "C6") (pin "1") (pinfunction "1_1") (pintype "passive"))
      (node (ref "C7") (pin "2") (pinfunction "2_2") (pintype "passive"))
      (node (ref "R1") (pin "1") (pinfunction "1_1") (pintype "passive"))
      (node (ref "R13") (pin "2") (pinfunction "2_2") (pintype "passive"))
      (node (ref "R16") (pin "2") (pinfunction "2_2") (pintype "passive"))
      (node (ref "R17") (pin "2") (pinfunction "2_2") (pintype "passive"))
      (node (ref "U1") (pin "1") (pinfunction "DRGND_1") (pintype "passive"))
      (node (ref "U1") (pin "12") (pinfunction "AGND_12") (pintype "passive"))
      (node (ref "U1") (pin "14") (pinfunction "AGND_14") (pintype "passive"))
      (node (ref "U1") (pin "17") (pinfunction "AGND_17") (pintype "passive"))
      (node (ref "U1") (pin "19") (pinfunction "AGND_19") (pintype "passive"))
      (node (ref "U1") (pin "25") (pinfunction "AGND_25") (pintype "passive"))
      (node (ref "U1") (pin "36") (pinfunction "DRGND_36") (pintype "passive"))
      (node (ref "U1") (pin "9") (pinfunction "AGND_9") (pintype "passive"))
      (node (ref "U1") (pin "EP") (pinfunction "EP_EP") (pintype "passive"))
      (node (ref "U2") (pin "EP") (pinfunction "EP_EP") (pintype "passive"))
      (node (ref "XT1") (pin "3") (pinfunction "GND_3") (pintype "passive"))
    )
    (net (code "36") (name "Net-(C1-Pad2)") (class "Default")
      (node (ref "C1") (pin "2") (pinfunction "2_2") (pintype "passive"))
      (node (ref "C3") (pin "1") (pinfunction "1_1") (pintype "passive"))
      (node (ref "R2") (pin "1") (pinfunction "1_1") (pintype "passive"))
      (node (ref "R6") (pin "2") (pinfunction "2_2") (pintype "passive"))
    )
    (net (code "37") (name "Net-(C2-Pad1)") (class "Default")
      (node (ref "C2") (pin "1") (pinfunction "1_1") (pintype "passive"))
      (node (ref "R4") (pin "2") (pinfunction "2_2") (pintype "passive"))
      (node (ref "R5") (pin "2") (pinfunction "2_2") (pintype "passive"))
      (node (ref "R7") (pin "2") (pinfunction "2_2") (pintype "passive"))
    )
    (net (code "38") (name "Net-(C9-Pad1)") (class "Default")
      (node (ref "C9") (pin "1") (pinfunction "1_1") (pintype "passive"))
      (node (ref "R10") (pin "2") (pinfunction "2_2") (pintype "passive"))
      (node (ref "R11") (pin "1") (pinfunction "1_1") (pintype "passive"))
      (node (ref "R9") (pin "1") (pinfunction "1_1") (pintype "passive"))
    )
    (net (code "39") (name "Net-(C10-Pad1)") (class "Default")
      (node (ref "C10") (pin "1") (pinfunction "1_1") (pintype "passive"))
      (node (ref "C8") (pin "2") (pinfunction "2_2") (pintype "passive"))
      (node (ref "R14") (pin "1") (pinfunction "1_1") (pintype "passive"))
      (node (ref "R8") (pin "1") (pinfunction "1_1") (pintype "passive"))
    )
    (net (code "40") (name "Net-(R1-Pad2)") (class "Default")
      (node (ref "R1") (pin "2") (pinfunction "2_2") (pintype "passive"))
      (node (ref "R2") (pin "2") (pinfunction "2_2") (pintype "passive"))
      (node (ref "R4") (pin "1") (pinfunction "1_1") (pintype "passive"))
    )
    (net (code "41") (name "Net-(R11-Pad2)") (class "Default")
      (node (ref "R11") (pin "2") (pinfunction "2_2") (pintype "passive"))
      (node (ref "R13") (pin "1") (pinfunction "1_1") (pintype "passive"))
      (node (ref "R14") (pin "2") (pinfunction "2_2") (pintype "passive"))
    )
    (net (code "42") (name "Net-(U1A-INM)") (class "Default")
      (node (ref "C8") (pin "1") (pinfunction "1_1") (pintype "passive"))
      (node (ref "U1") (pin "16") (pinfunction "INM_16") (pintype "passive"))
    )
    (net (code "43") (name "Net-(U1A-INP)") (class "Default")
      (node (ref "C1") (pin "1") (pinfunction "1_1") (pintype "passive"))
      (node (ref "U1") (pin "15") (pinfunction "INP_15") (pintype "passive"))
    )
    (net (code "44") (name "Net-(U1B-AVDD_BUF)") (class "Default")
      (node (ref "C28") (pin "1") (pinfunction "1_1") (pintype "passive"))
      (node (ref "R20") (pin "2") (pinfunction "2_2") (pintype "passive"))
      (node (ref "U1") (pin "21") (pinfunction "AVDD_BUF_21") (pintype "passive"))
    )
    (net (code "45") (name "Net-(U2A-+FB1)") (class "Default")
      (node (ref "R12") (pin "1") (pinfunction "1_1") (pintype "passive"))
      (node (ref "U2") (pin "4") (pinfunction "+FB1_4") (pintype "passive"))
    )
    (net (code "46") (name "Net-(U2A-+IN1)") (class "Default")
      (node (ref "R3") (pin "2") (pinfunction "2_2") (pintype "passive"))
      (node (ref "R5") (pin "1") (pinfunction "1_1") (pintype "passive"))
      (node (ref "U2") (pin "2") (pinfunction "+IN1_2") (pintype "passive"))
    )
    (net (code "47") (name "Net-(U2A-+OUT1)") (class "Default")
      (node (ref "C10") (pin "2") (pinfunction "2_2") (pintype "passive"))
      (node (ref "U2") (pin "10") (pinfunction "+OUT1_10") (pintype "passive"))
    )
    (net (code "48") (name "Net-(U2A--FB1)") (class "Default")
      (node (ref "R3") (pin "1") (pinfunction "1_1") (pintype "passive"))
      (node (ref "U2") (pin "1") (pinfunction "-FB1_1") (pintype "passive"))
    )
    (net (code "49") (name "Net-(U2A--IN1)") (class "Default")
      (node (ref "R10") (pin "1") (pinfunction "1_1") (pintype "passive"))
      (node (ref "R12") (pin "2") (pinfunction "2_2") (pintype "passive"))
      (node (ref "U2") (pin "3") (pinfunction "-IN1_3") (pintype "passive"))
    )
    (net (code "50") (name "Net-(U2A--OUT1)") (class "Default")
      (node (ref "C3") (pin "2") (pinfunction "2_2") (pintype "passive"))
      (node (ref "U2") (pin "11") (pinfunction "-OUT1_11") (pintype "passive"))
    )
    (net (code "51") (name "Net-(U2B-~{PD})") (class "Default")
      (node (ref "R23") (pin "2") (pinfunction "2_2") (pintype "passive"))
      (node (ref "U2") (pin "12") (pinfunction "~{PD}_12") (pintype "passive"))
    )
    (net (code "52") (name "unconnected-(U1B-NC-Pad31)") (class "Default")
      (node (ref "U1") (pin "31") (pinfunction "NC_31") (pintype "passive+no_connect"))
    )
    (net (code "53") (name "unconnected-(U1B-NC-Pad32)") (class "Default")
      (node (ref "U1") (pin "32") (pinfunction "NC_32") (pintype "passive+no_connect"))
    )
    (net (code "54") (name "unconnected-(U1B-NC-Pad33)") (class "Default")
      (node (ref "U1") (pin "33") (pinfunction "NC_33") (pintype "passive+no_connect"))
    )
    (net (code "55") (name "unconnected-(U1B-NC-Pad34)") (class "Default")
      (node (ref "U1") (pin "34") (pinfunction "NC_34") (pintype "passive+no_connect"))
    )
    (net (code "56") (name "unconnected-(XT1-NC{slash}EN-Pad2)") (class "Default")
      (node (ref "XT1") (pin "2") (pinfunction "NC/EN_2") (pintype "passive+no_connect"))
    )
  )
)
